# Power.net
KiCad netlist of a schematic drawn in Altium Designer
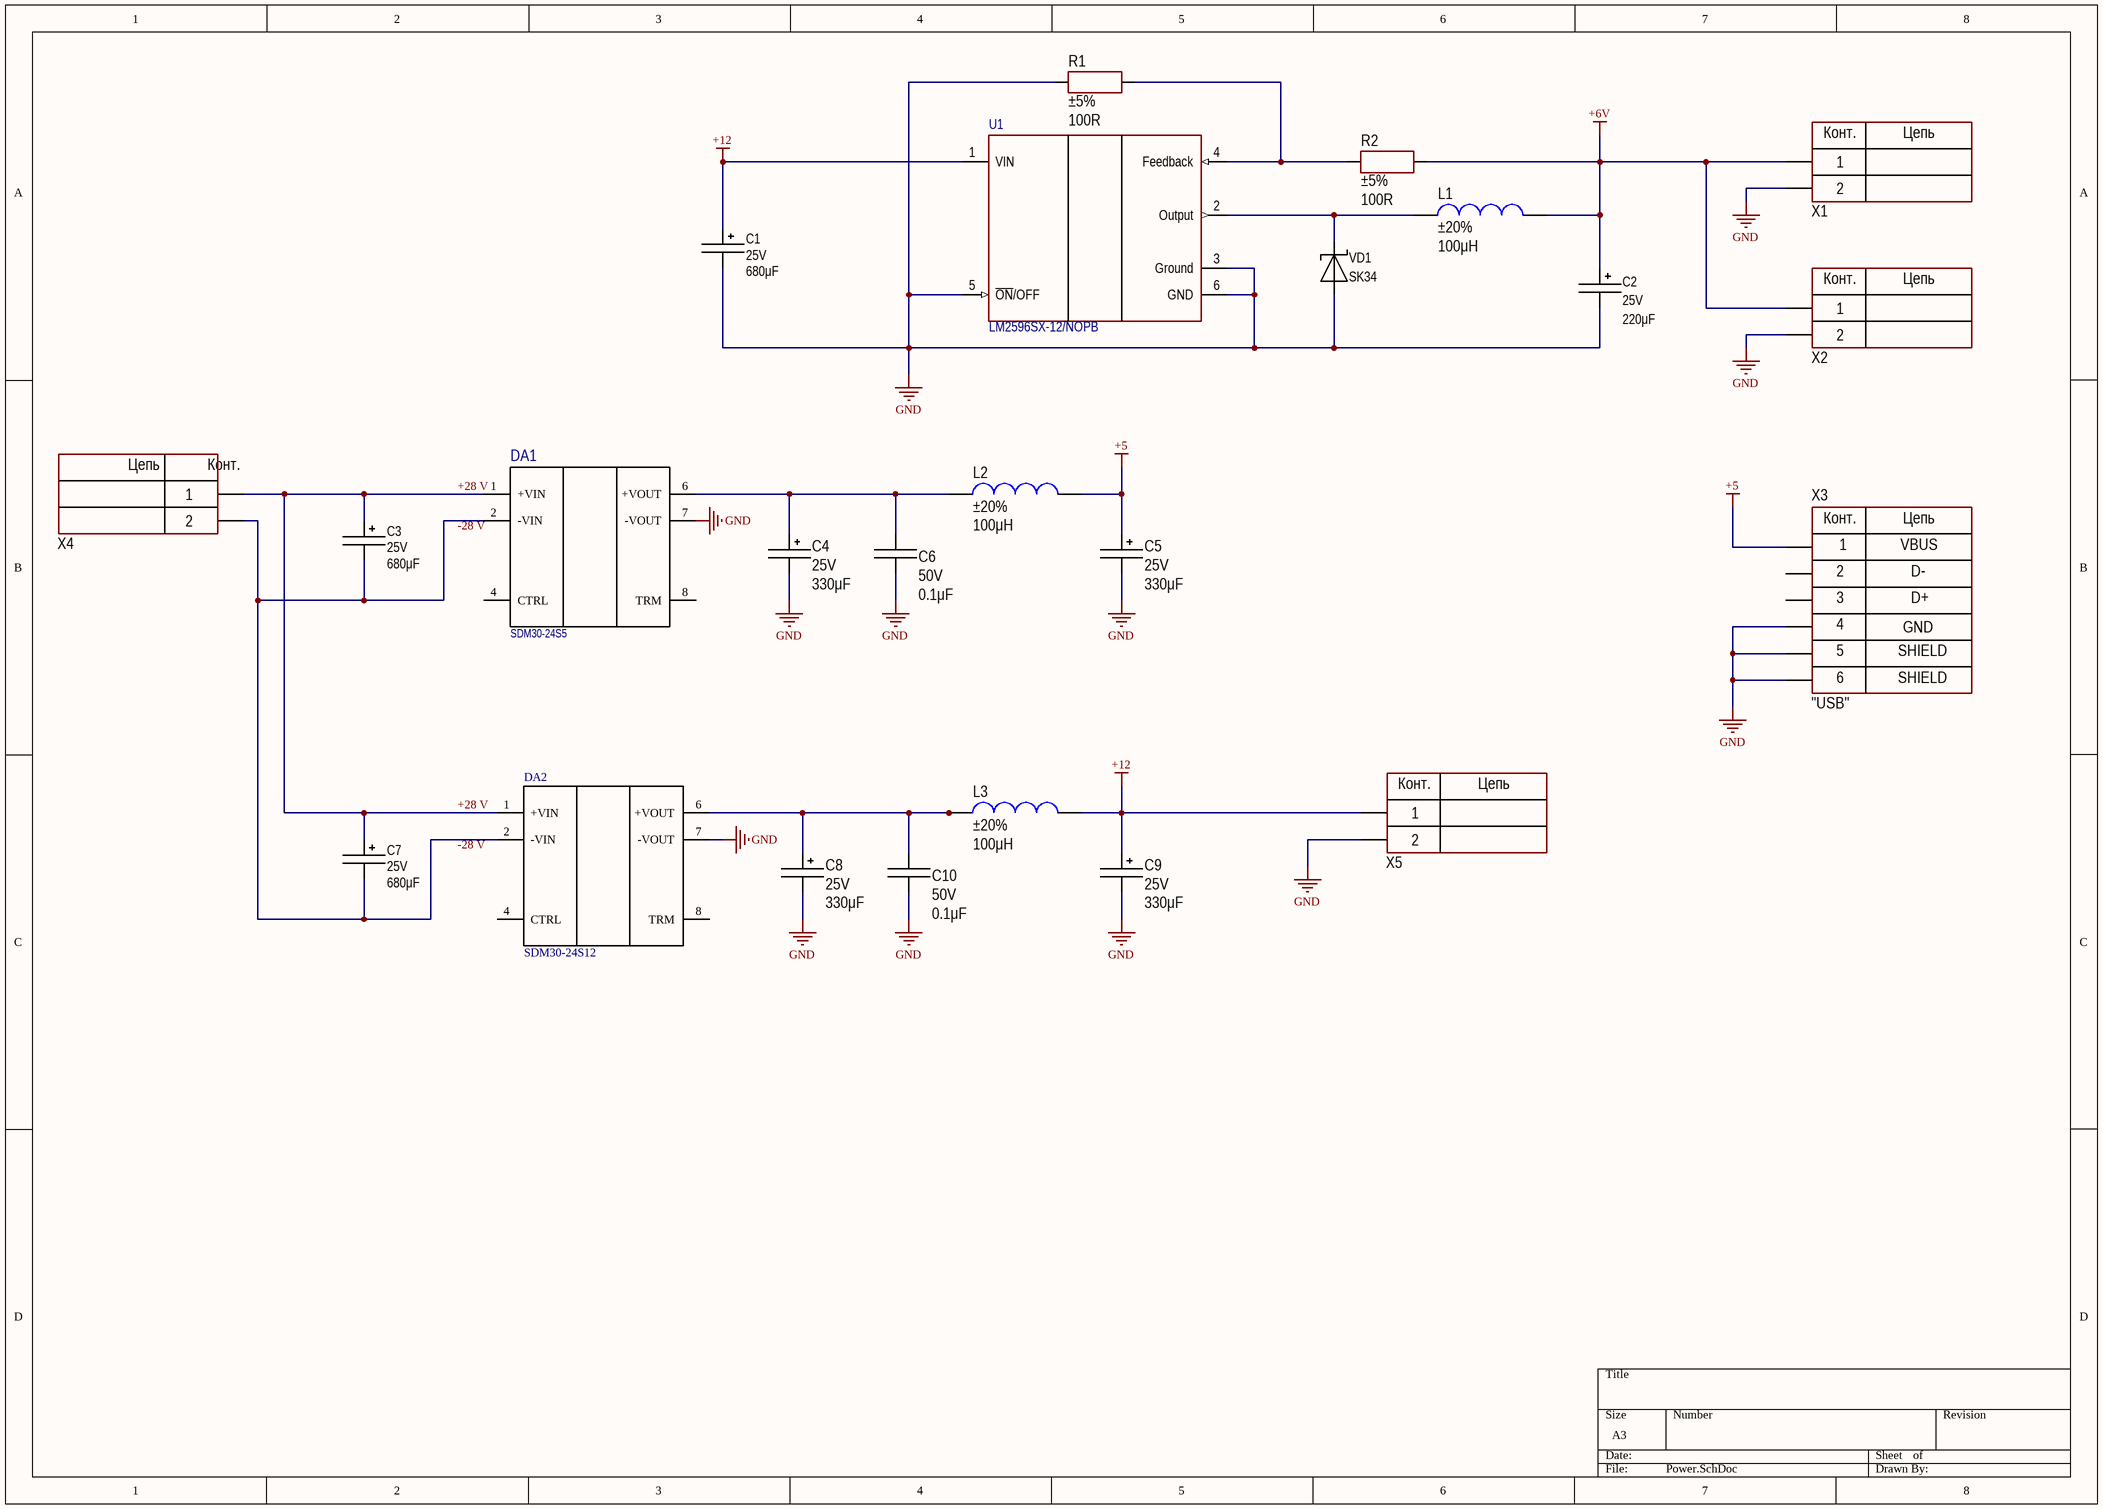
[diagram p0: Power.SchDoc]

(export (version "E")
  (design (tool "Eeschema 10.0.6"))
  (components
    (comp (ref "C1")
      (value "680μF")
      (footprint "standard-case:CAP: D10C5H16")
      (fields
        (field (name "MANUFACTURER") "Wurth")
        (field (name "PARTNUMBER") "860080475013")
        (field (name "VALUEMANUFACTURERPARTNUMBER") "Aluminium capacitor, 680μF, 25V, ±20%, 54mOhm, 14x10x5 mm, -55...+105°C")
        (field (name "VOLTAGE") "25V")
      )
      (libsource (lib "capacitor") (part "Aluminium"))
    )
    (comp (ref "C2")
      (value "220μF")
      (footprint "standard-case:CAP: D10C5H16")
      (fields
        (field (name "MANUFACTURER") "Wurth")
        (field (name "PARTNUMBER") "860080475013")
        (field (name "VALUEMANUFACTURERPARTNUMBER") "Aluminium capacitor, 220μF, 25V, ±20%, 54mOhm, 14x10x5 mm, -55...+105°C")
        (field (name "VOLTAGE") "25V")
      )
      (libsource (lib "capacitor") (part "Aluminium"))
    )
    (comp (ref "C3")
      (value "680μF")
      (footprint "standard-case:CAP: D10C5H16")
      (fields
        (field (name "MANUFACTURER") "Wurth")
        (field (name "PARTNUMBER") "860080475013")
        (field (name "VALUEMANUFACTURERPARTNUMBER") "Aluminium capacitor, 680μF, 25V, ±20%, 54mOhm, 14x10x5 mm, -55...+105°C")
        (field (name "VOLTAGE") "25V")
      )
      (libsource (lib "capacitor") (part "Aluminium"))
    )
    (comp (ref "C4")
      (value "330μF")
      (footprint "standard-case:CAP: D6.3C2.5H11")
      (fields
        (field (name "MANUFACTURER") "Wurth")
        (field (name "PARTNUMBER") "860080475013")
        (field (name "VALUEMANUFACTURERPARTNUMBER") "Aluminium capacitor, 330μF, 25V, ±20%, 54mOhm, 14x10x5 mm, -55...+105°C")
        (field (name "VOLTAGE") "25V")
      )
      (libsource (lib "capacitor") (part "Aluminium"))
    )
    (comp (ref "C5")
      (value "330μF")
      (footprint "standard-case:CAP: D6.3C2.5H11")
      (fields
        (field (name "MANUFACTURER") "Wurth")
        (field (name "PARTNUMBER") "860080475013")
        (field (name "VALUEMANUFACTURERPARTNUMBER") "Aluminium capacitor, 330μF, 25V, ±20%, 54mOhm, 14x10x5 mm, -55...+105°C")
        (field (name "VOLTAGE") "25V")
      )
      (libsource (lib "capacitor") (part "Aluminium"))
    )
    (comp (ref "C6")
      (value "0.1μF")
      (footprint "standard-case:CAP: 1206")
      (fields
        (field (name "MANUFACTURER") "Yageo")
        (field (name "PARTNUMBER") "CC1206KRX7R9BB104")
        (field (name "VALUEMANUFACTURERPARTNUMBER") "Ceramic capacitor, 0.1μF, X7R, ±10%, 50V, 1206, -55...+125°C")
        (field (name "VOLTAGE") "50V")
      )
      (libsource (lib "capacitor") (part "Ceramic_1206"))
    )
    (comp (ref "C7")
      (value "680μF")
      (footprint "standard-case:CAP: D10C5H16")
      (fields
        (field (name "MANUFACTURER") "Wurth")
        (field (name "PARTNUMBER") "860080475013")
        (field (name "VALUEMANUFACTURERPARTNUMBER") "Aluminium capacitor, 680μF, 25V, ±20%, 54mOhm, 14x10x5 mm, -55...+105°C")
        (field (name "VOLTAGE") "25V")
      )
      (libsource (lib "capacitor") (part "Aluminium"))
    )
    (comp (ref "C8")
      (value "330μF")
      (footprint "standard-case:CAP: D6.3C2.5H11")
      (fields
        (field (name "MANUFACTURER") "Wurth")
        (field (name "PARTNUMBER") "860080475013")
        (field (name "VALUEMANUFACTURERPARTNUMBER") "Aluminium capacitor, 330μF, 25V, ±20%, 54mOhm, 14x10x5 mm, -55...+105°C")
        (field (name "VOLTAGE") "25V")
      )
      (libsource (lib "capacitor") (part "Aluminium"))
    )
    (comp (ref "C9")
      (value "330μF")
      (footprint "standard-case:CAP: D6.3C2.5H11")
      (fields
        (field (name "MANUFACTURER") "Wurth")
        (field (name "PARTNUMBER") "860080475013")
        (field (name "VALUEMANUFACTURERPARTNUMBER") "Aluminium capacitor, 330μF, 25V, ±20%, 54mOhm, 14x10x5 mm, -55...+105°C")
        (field (name "VOLTAGE") "25V")
      )
      (libsource (lib "capacitor") (part "Aluminium"))
    )
    (comp (ref "C10")
      (value "0.1μF")
      (footprint "standard-case:CAP: 1206")
      (fields
        (field (name "MANUFACTURER") "Yageo")
        (field (name "PARTNUMBER") "CC1206KRX7R9BB104")
        (field (name "VALUEMANUFACTURERPARTNUMBER") "Ceramic capacitor, 0.1μF, X7R, ±10%, 50V, 1206, -55...+125°C")
        (field (name "VOLTAGE") "50V")
      )
      (libsource (lib "capacitor") (part "Ceramic_1206"))
    )
    (comp (ref "DA1")
      (value "SDM30-24S5")
      (footprint "SDM3024S5")
      (description "Power Supply")
      (libsource (lib "SDM30-24S5") (part "SDM30-24S5"))
    )
    (comp (ref "DA2")
      (value "SDM30-24S12")
      (footprint "SDM3024S12")
      (description "Power Supply")
      (libsource (lib "SDM30-24S12") (part "SDM30-24S12"))
    )
    (comp (ref "L1")
      (value "100μH")
      (footprint "SRR1208-101YL")
      (fields
        (field (name "MANUFACTURER") "Bourns")
        (field (name "PARTNUMBER") "SDR0403-4R7ML")
        (field (name "VALUEMANUFACTURERPARTNUMBER") "Fixed inductor, 100μH, ±20%, SDR0403, 1.7A, -40...+125°C")
        (field (name "TOLERANCE") "±20%")
      )
      (libsource (lib "SRR1208-101YL") (part "Inductor_SDR0403"))
    )
    (comp (ref "L2")
      (value "100μH")
      (footprint "SRR1208-101YL")
      (fields
        (field (name "MANUFACTURER") "Bourns")
        (field (name "PARTNUMBER") "SDR0403-4R7ML")
        (field (name "VALUEMANUFACTURERPARTNUMBER") "Fixed inductor, 100μH, ±20%, SDR0403, 1.7A, -40...+125°C")
        (field (name "TOLERANCE") "±20%")
      )
      (libsource (lib "SRR1208-101YL") (part "Inductor_SDR0403"))
    )
    (comp (ref "L3")
      (value "100μH")
      (footprint "SRR1208-101YL")
      (fields
        (field (name "MANUFACTURER") "Bourns")
        (field (name "PARTNUMBER") "SDR0403-4R7ML")
        (field (name "VALUEMANUFACTURERPARTNUMBER") "Fixed inductor, 100μH, ±20%, SDR0403, 1.7A, -40...+125°C")
        (field (name "TOLERANCE") "±20%")
      )
      (libsource (lib "SRR1208-101YL") (part "Inductor_SDR0403"))
    )
    (comp (ref "R1")
      (value "100R")
      (footprint "standard-case:RES: 1206")
      (fields
        (field (name "MANUFACTURER") "Yageo")
        (field (name "PARTNUMBER") "RC1206JR-07100RL")
        (field (name "VALUEMANUFACTURERPARTNUMBER") "Resistor film, 100R, ±5%, 1206, 0.25W, -55...+125°C")
        (field (name "TOLERANCE") "±5%")
      )
      (libsource (lib "resistor") (part "Resistor_1206"))
    )
    (comp (ref "R2")
      (value "100R")
      (footprint "standard-case:RES: 1206")
      (fields
        (field (name "MANUFACTURER") "Yageo")
        (field (name "PARTNUMBER") "RC1206JR-07100RL")
        (field (name "VALUEMANUFACTURERPARTNUMBER") "Resistor film, 100R, ±5%, 1206, 0.25W, -55...+125°C")
        (field (name "TOLERANCE") "±5%")
      )
      (libsource (lib "resistor") (part "Resistor_1206"))
    )
    (comp (ref "U1")
      (value "LM2596SX-12/NOPB")
      (footprint "FP-KTT0005B-MFG")
      (description "IC REG BUCK 12V 3A TO263-5")
      (fields
        (field (name "MANUFACTURER") "Texas Instruments")
        (field (name "OCTOPART") "https://octopart.com/lm2596sx-12%2Fnopb-texas+instruments-24812942")
      )
      (libsource (lib "LM2596SX-12NOPB") (part "CMP-04918-000013-1"))
    )
    (comp (ref "VD1")
      (value "~")
      (footprint "standard-case:DIODE: SMC")
      (fields
        (field (name "MANUFACTURER") "Diodes Incorporated")
        (field (name "VALUEMANUFACTURERPARTNUMBER") "Schottky diode, 80V, 500mA, 1V, 15pF, SOD-123, -55...+150°C")
        (field (name "VOLTAGE") "80V")
        (field (name "PARTNUMBER") "SK34")
      )
      (libsource (lib "diode") (part "Schottky_single"))
    )
    (comp (ref "X1")
      (value "~")
      (footprint "2EDGR-5.08-02P")
      (fields
        (field (name "MANUFACTURER") "Connfly")
        (field (name "VALUEMANUFACTURERPARTNUMBER") "Connector, 6pin, 2.54mm, 500VAC, 3A")
        (field (name "PARTNUMBER") "PBS-6")
      )
      (libsource (lib "K3NG_SCH_Libs") (part "2EDGR-5.08-02P"))
    )
    (comp (ref "X2")
      (value "~")
      (footprint "2EDGR-5.08-02P")
      (fields
        (field (name "MANUFACTURER") "Connfly")
        (field (name "VALUEMANUFACTURERPARTNUMBER") "Connector, 6pin, 2.54mm, 500VAC, 3A")
        (field (name "PARTNUMBER") "PBS-6")
      )
      (libsource (lib "K3NG_SCH_Libs") (part "2EDGR-5.08-02P"))
    )
    (comp (ref "X3")
      (value "~")
      (footprint "FP-292303-4-MFG")
      (fields
        (field (name "MANUFACTURER") "Hirose Electric")
        (field (name "VALUEMANUFACTURERPARTNUMBER") "USB micro B")
        (field (name "PARTNUMBER") "ZX62-B-5PA")
        (field (name "COMMENTTEXT") "\"USB\"")
      )
      (libsource (lib "292303-4") (part "Connector_USB_micro_B"))
    )
    (comp (ref "X4")
      (value "~")
      (footprint "2EDGR-5.08-02P")
      (fields
        (field (name "MANUFACTURER") "Connfly")
        (field (name "VALUEMANUFACTURERPARTNUMBER") "Connector, 6pin, 2.54mm, 500VAC, 3A")
        (field (name "PARTNUMBER") "PBS-6")
      )
      (libsource (lib "") (part "2EDGR-5.08-02P_1"))
    )
    (comp (ref "X5")
      (value "~")
      (footprint "2EDGR-5.08-02P")
      (fields
        (field (name "MANUFACTURER") "Connfly")
        (field (name "VALUEMANUFACTURERPARTNUMBER") "Connector, 6pin, 2.54mm, 500VAC, 3A")
        (field (name "PARTNUMBER") "PBS-6")
      )
      (libsource (lib "K3NG_SCH_Libs") (part "2EDGR-5.08-02P"))
    )
  )
  (nets
    (net (code "1") (name "+5") (class "Default")
      (node (ref "C5") (pin "1") (pinfunction "1_1") (pintype "passive"))
      (node (ref "L2") (pin "1") (pinfunction "1_1") (pintype "passive"))
      (node (ref "X3") (pin "1") (pintype "passive"))
    )
    (net (code "2") (name "+6V") (class "Default")
      (node (ref "C2") (pin "1") (pinfunction "1_1") (pintype "passive"))
      (node (ref "L1") (pin "1") (pinfunction "1_1") (pintype "passive"))
      (node (ref "R2") (pin "2") (pinfunction "2_2") (pintype "passive"))
      (node (ref "X1") (pin "1") (pinfunction "1_1") (pintype "passive"))
      (node (ref "X2") (pin "1") (pinfunction "1_1") (pintype "passive"))
    )
    (net (code "3") (name "+12") (class "Default")
      (node (ref "C1") (pin "1") (pinfunction "1_1") (pintype "passive"))
      (node (ref "C9") (pin "1") (pinfunction "1_1") (pintype "passive"))
      (node (ref "L3") (pin "1") (pinfunction "1_1") (pintype "passive"))
      (node (ref "U1") (pin "1") (pinfunction "VIN_1") (pintype "power_in"))
      (node (ref "X5") (pin "1") (pinfunction "1_1") (pintype "passive"))
    )
    (net (code "4") (name "/+28 V") (class "Default")
      (node (ref "C3") (pin "1") (pinfunction "1_1") (pintype "passive"))
      (node (ref "C7") (pin "1") (pinfunction "1_1") (pintype "passive"))
      (node (ref "DA1") (pin "1") (pinfunction "+VIN_1") (pintype "passive"))
      (node (ref "DA2") (pin "1") (pinfunction "+VIN_1") (pintype "passive"))
      (node (ref "X4") (pin "1") (pinfunction "1_1") (pintype "passive"))
    )
    (net (code "6") (name "GND") (class "Default")
      (node (ref "C1") (pin "2") (pinfunction "2_2") (pintype "passive"))
      (node (ref "C10") (pin "1") (pinfunction "1_1") (pintype "passive"))
      (node (ref "C2") (pin "2") (pinfunction "2_2") (pintype "passive"))
      (node (ref "C4") (pin "2") (pinfunction "2_2") (pintype "passive"))
      (node (ref "C5") (pin "2") (pinfunction "2_2") (pintype "passive"))
      (node (ref "C6") (pin "1") (pinfunction "1_1") (pintype "passive"))
      (node (ref "C8") (pin "2") (pinfunction "2_2") (pintype "passive"))
      (node (ref "C9") (pin "2") (pinfunction "2_2") (pintype "passive"))
      (node (ref "DA1") (pin "7") (pinfunction "-VOUT_7") (pintype "passive"))
      (node (ref "DA2") (pin "7") (pinfunction "-VOUT_7") (pintype "passive"))
      (node (ref "R1") (pin "1") (pinfunction "1_1") (pintype "passive"))
      (node (ref "U1") (pin "3") (pinfunction "Ground_3") (pintype "power_in"))
      (node (ref "U1") (pin "5") (pinfunction "~{ON}/OFF_5") (pintype "input"))
      (node (ref "U1") (pin "6") (pinfunction "GND_6") (pintype "power_in"))
      (node (ref "VD1") (pin "1") (pinfunction "1_1") (pintype "passive"))
      (node (ref "X1") (pin "2") (pinfunction "2_2") (pintype "passive"))
      (node (ref "X2") (pin "2") (pinfunction "2_2") (pintype "passive"))
      (node (ref "X3") (pin "4") (pinfunction "4_4") (pintype "passive"))
      (node (ref "X3") (pin "5") (pinfunction "5_5") (pintype "passive"))
      (node (ref "X3") (pin "6") (pinfunction "6_6") (pintype "passive"))
      (node (ref "X5") (pin "2") (pinfunction "2_2") (pintype "passive"))
    )
    (net (code "7") (name "Net-(DA1-+VOUT)") (class "Default")
      (node (ref "C4") (pin "1") (pinfunction "1_1") (pintype "passive"))
      (node (ref "C6") (pin "2") (pinfunction "2_2") (pintype "passive"))
      (node (ref "DA1") (pin "6") (pinfunction "+VOUT_6") (pintype "passive"))
      (node (ref "L2") (pin "2") (pinfunction "2_2") (pintype "passive"))
    )
    (net (code "8") (name "Net-(DA1--VIN)") (class "Default")
      (node (ref "C3") (pin "2") (pinfunction "2_2") (pintype "passive"))
      (node (ref "C7") (pin "2") (pinfunction "2_2") (pintype "passive"))
      (node (ref "DA1") (pin "2") (pinfunction "-VIN_2") (pintype "passive"))
      (node (ref "DA2") (pin "2") (pinfunction "-VIN_2") (pintype "passive"))
      (node (ref "X4") (pin "2") (pinfunction "2_2") (pintype "passive"))
    )
    (net (code "9") (name "Net-(DA2-+VOUT)") (class "Default")
      (node (ref "C10") (pin "2") (pinfunction "2_2") (pintype "passive"))
      (node (ref "C8") (pin "1") (pinfunction "1_1") (pintype "passive"))
      (node (ref "DA2") (pin "6") (pinfunction "+VOUT_6") (pintype "passive"))
      (node (ref "L3") (pin "2") (pinfunction "2_2") (pintype "passive"))
    )
    (net (code "10") (name "Net-(U1-Feedback)") (class "Default")
      (node (ref "R1") (pin "2") (pinfunction "2_2") (pintype "passive"))
      (node (ref "R2") (pin "1") (pinfunction "1_1") (pintype "passive"))
      (node (ref "U1") (pin "4") (pinfunction "Feedback_4") (pintype "input"))
    )
    (net (code "11") (name "Net-(U1-Output)") (class "Default")
      (node (ref "L1") (pin "2") (pinfunction "2_2") (pintype "passive"))
      (node (ref "U1") (pin "2") (pinfunction "Output_2") (pintype "output"))
      (node (ref "VD1") (pin "2") (pinfunction "2_2") (pintype "passive"))
    )
    (net (code "12") (name "unconnected-(DA1-CTRL-Pad4)") (class "Default")
      (node (ref "DA1") (pin "4") (pinfunction "CTRL_4") (pintype "passive"))
    )
    (net (code "13") (name "unconnected-(DA1-TRM-Pad8)") (class "Default")
      (node (ref "DA1") (pin "8") (pinfunction "TRM_8") (pintype "passive"))
    )
    (net (code "14") (name "unconnected-(DA2-CTRL-Pad4)") (class "Default")
      (node (ref "DA2") (pin "4") (pinfunction "CTRL_4") (pintype "passive"))
    )
    (net (code "15") (name "unconnected-(DA2-TRM-Pad8)") (class "Default")
      (node (ref "DA2") (pin "8") (pinfunction "TRM_8") (pintype "passive"))
    )
    (net (code "16") (name "unconnected-(X3-Pad2)") (class "Default")
      (node (ref "X3") (pin "2") (pinfunction "2_2") (pintype "passive"))
    )
    (net (code "17") (name "unconnected-(X3-Pad3)") (class "Default")
      (node (ref "X3") (pin "3") (pinfunction "3_3") (pintype "passive"))
    )
  )
)
